# APC1.net
KiCad netlist of a schematic drawn in EAGLE
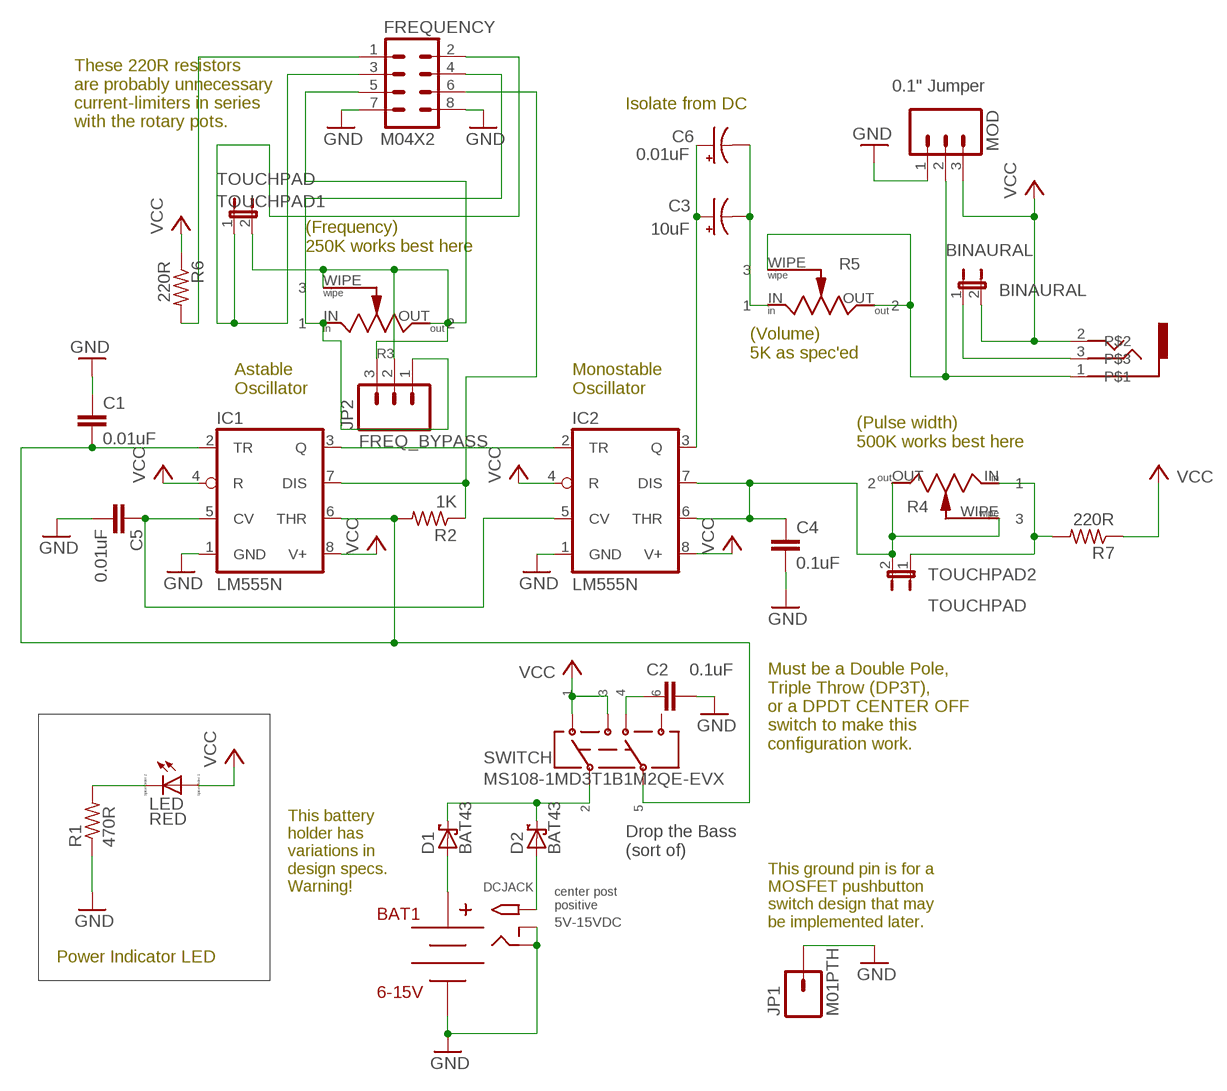
[diagram p0: schematic, sheet 1]

(export (version "E")
  (design (tool "Eeschema 10.0.6"))
  (components
    (comp (ref "BAT1")
      (value "6-15V")
      (footprint "eagle-import:BH9VPC")
      (libsource (lib "eagle-import") (part "BH-9VPC"))
    )
    (comp (ref "BINAURAL")
      (value "BINAURAL")
      (footprint "eagle-import:JP1")
      (libsource (lib "eagle-import") (part "JP1E"))
    )
    (comp (ref "C1")
      (value "0.01uF")
      (footprint "eagle-import:C050-024X044")
      (libsource (lib "eagle-import") (part "C-EU050-024X044"))
    )
    (comp (ref "C2")
      (value "0.1uF")
      (footprint "eagle-import:C050-024X044")
      (libsource (lib "eagle-import") (part "C-EU050-024X044"))
    )
    (comp (ref "C3")
      (value "10uF")
      (footprint "eagle-import:E2,5-7")
      (libsource (lib "eagle-import") (part "CPOL-USE2.5-7"))
    )
    (comp (ref "C4")
      (value "0.1uF")
      (footprint "eagle-import:C050-024X044")
      (libsource (lib "eagle-import") (part "C-EU050-024X044"))
    )
    (comp (ref "C5")
      (value "0.01uF")
      (footprint "eagle-import:C050-024X044")
      (libsource (lib "eagle-import") (part "C-EU050-024X044"))
    )
    (comp (ref "C6")
      (value "0.01uF")
      (footprint "eagle-import:E2,5-7")
      (libsource (lib "eagle-import") (part "CPOL-USE2.5-7"))
    )
    (comp (ref "D1")
      (value "BAT43")
      (footprint "eagle-import:DO35-7")
      (libsource (lib "eagle-import") (part "SCHOTTKY-DIODEDO35-7"))
    )
    (comp (ref "D2")
      (value "BAT43")
      (footprint "eagle-import:DO35-7")
      (libsource (lib "eagle-import") (part "SCHOTTKY-DIODEDO35-7"))
    )
    (comp (ref "DCJACK")
      (value "PJ102A")
      (footprint "eagle-import:PJ-102A")
      (libsource (lib "eagle-import") (part "PJ102A"))
    )
    (comp (ref "FREQUENCY")
      (value "M04X2")
      (footprint "eagle-import:2X4")
      (libsource (lib "eagle-import") (part "M04X2"))
    )
    (comp (ref "IC1")
      (value "LM555N")
      (footprint "eagle-import:DIL08")
      (libsource (lib "eagle-import") (part "555NLM"))
    )
    (comp (ref "IC2")
      (value "LM555N")
      (footprint "eagle-import:DIL08")
      (libsource (lib "eagle-import") (part "555NLM"))
    )
    (comp (ref "JP1")
      (value "M01PTH")
      (footprint "eagle-import:1X01")
      (libsource (lib "eagle-import") (part "M01PTH"))
    )
    (comp (ref "JP2")
      (value "FREQ_BYPASS")
      (footprint "eagle-import:1X03_SMD_RA_MALE")
      (libsource (lib "eagle-import") (part "M03SMD_RA_MALE"))
    )
    (comp (ref "LED")
      (value "RED")
      (footprint "eagle-import:LED_LD260")
      (libsource (lib "eagle-import") (part "LED_ELD260"))
    )
    (comp (ref "LINE")
      (value "SJ-3523-SMT")
      (footprint "eagle-import:SJ352_AUDIOJACK")
      (libsource (lib "eagle-import") (part "SJ-3523-SMT"))
    )
    (comp (ref "MOD")
      (value "0.1\" Jumper")
      (footprint "eagle-import:1X03_LOCK")
      (libsource (lib "eagle-import") (part "M03LOCK"))
    )
    (comp (ref "R1")
      (value "470R")
      (footprint "eagle-import:0207_7")
      (libsource (lib "eagle-import") (part "R-US_0207/7"))
    )
    (comp (ref "R2")
      (value "1K")
      (footprint "eagle-import:0207_7")
      (libsource (lib "eagle-import") (part "R-US_0207/7"))
    )
    (comp (ref "R3")
      (value "CTS_UM296RE_SERIES_POTENTIOMETERUM296RE")
      (footprint "eagle-import:UM296RE_POTENTIOMETER")
      (libsource (lib "eagle-import") (part "CTS_UM296RE_SERIES_POTENTIOMETERUM296RE"))
    )
    (comp (ref "R4")
      (value "CTS_UM296RE_SERIES_POTENTIOMETERUM296RE")
      (footprint "eagle-import:UM296RE_POTENTIOMETER")
      (libsource (lib "eagle-import") (part "CTS_UM296RE_SERIES_POTENTIOMETERUM296RE"))
    )
    (comp (ref "R5")
      (value "CTS_UM296RE_SERIES_POTENTIOMETERUM296RE")
      (footprint "eagle-import:UM296RE_POTENTIOMETER")
      (libsource (lib "eagle-import") (part "CTS_UM296RE_SERIES_POTENTIOMETERUM296RE"))
    )
    (comp (ref "R6")
      (value "220R")
      (footprint "eagle-import:0207_7")
      (libsource (lib "eagle-import") (part "R-US_0207/7"))
    )
    (comp (ref "R7")
      (value "220R")
      (footprint "eagle-import:0207_7")
      (libsource (lib "eagle-import") (part "R-US_0207/7"))
    )
    (comp (ref "SWITCH")
      (value "MS108-1MD3T1B1M2QE-EVX")
      (footprint "eagle-import:MS108-1MD3T1B1M2QE-EVX")
      (libsource (lib "eagle-import") (part "MS108-1MD3T1B1M2QE-EVX"))
    )
    (comp (ref "TOUCHPAD1")
      (value "TOUCHPAD")
      (footprint "eagle-import:JP1")
      (libsource (lib "eagle-import") (part "JP1E"))
    )
    (comp (ref "TOUCHPAD2")
      (value "TOUCHPAD")
      (footprint "eagle-import:JP1")
      (libsource (lib "eagle-import") (part "JP1E"))
    )
  )
  (nets
    (net (code "1") (name "GND") (class "Default")
      (node (ref "BAT1") (pin "P$1") (pinfunction "V-_P$1") (pintype "power_in"))
      (node (ref "C1") (pin "1") (pinfunction "1_1") (pintype "passive"))
      (node (ref "C2") (pin "2") (pinfunction "2_2") (pintype "passive"))
      (node (ref "C4") (pin "2") (pinfunction "2_2") (pintype "passive"))
      (node (ref "C5") (pin "2") (pinfunction "2_2") (pintype "passive"))
      (node (ref "DCJACK") (pin "P$2") (pinfunction "RING_P$2") (pintype "bidirectional"))
      (node (ref "DCJACK") (pin "P$3") (pinfunction "RING_SW_P$3") (pintype "bidirectional"))
      (node (ref "FREQUENCY") (pin "7") (pinfunction "7_7") (pintype "passive"))
      (node (ref "FREQUENCY") (pin "8") (pinfunction "8_8") (pintype "passive"))
      (node (ref "IC1") (pin "1") (pinfunction "GND_1") (pintype "power_in"))
      (node (ref "IC2") (pin "1") (pinfunction "GND_1") (pintype "power_in"))
      (node (ref "JP1") (pin "1") (pinfunction "1_1") (pintype "passive"))
      (node (ref "MOD") (pin "1") (pinfunction "1_1") (pintype "passive"))
      (node (ref "R1") (pin "1") (pinfunction "1_1") (pintype "passive"))
    )
    (net (code "2") (name "Net-(BAT1-V+)") (class "Default")
      (node (ref "BAT1") (pin "P$2") (pinfunction "V+_P$2") (pintype "power_in"))
      (node (ref "D1") (pin "A") (pinfunction "A_A") (pintype "passive"))
    )
    (net (code "3") (name "Net-(DCJACK-TIP)") (class "Default")
      (node (ref "D2") (pin "A") (pinfunction "A_A") (pintype "passive"))
      (node (ref "DCJACK") (pin "P$1") (pinfunction "TIP_P$1") (pintype "bidirectional"))
    )
    (net (code "4") (name "Net-(FREQUENCY-Pad1)") (class "Default")
      (node (ref "FREQUENCY") (pin "1") (pinfunction "1_1") (pintype "passive"))
      (node (ref "R6") (pin "2") (pinfunction "2_2") (pintype "passive"))
    )
    (net (code "5") (name "Net-(FREQUENCY-Pad2)") (class "Default")
      (node (ref "FREQUENCY") (pin "2") (pinfunction "2_2") (pintype "passive"))
      (node (ref "FREQUENCY") (pin "3") (pinfunction "3_3") (pintype "passive"))
      (node (ref "TOUCHPAD1") (pin "1") (pinfunction "1_1") (pintype "passive"))
    )
    (net (code "6") (name "Net-(IC1-CV)") (class "Default")
      (node (ref "C5") (pin "1") (pinfunction "1_1") (pintype "passive"))
      (node (ref "IC1") (pin "5") (pinfunction "CV_5") (pintype "input"))
      (node (ref "IC2") (pin "5") (pinfunction "CV_5") (pintype "input"))
    )
    (net (code "7") (name "Net-(IC1-DIS)") (class "Default")
      (node (ref "FREQUENCY") (pin "6") (pinfunction "6_6") (pintype "passive"))
      (node (ref "IC1") (pin "7") (pinfunction "DIS_7") (pintype "input"))
      (node (ref "R2") (pin "1") (pinfunction "1_1") (pintype "passive"))
    )
    (net (code "8") (name "Net-(IC1-Q)") (class "Default")
      (node (ref "IC1") (pin "3") (pinfunction "Q_3") (pintype "output"))
      (node (ref "IC2") (pin "2") (pinfunction "TR_2") (pintype "input"))
    )
    (net (code "9") (name "Net-(IC1-THR)") (class "Default")
      (node (ref "C1") (pin "2") (pinfunction "2_2") (pintype "passive"))
      (node (ref "IC1") (pin "2") (pinfunction "TR_2") (pintype "input"))
      (node (ref "IC1") (pin "6") (pinfunction "THR_6") (pintype "input"))
      (node (ref "R2") (pin "2") (pinfunction "2_2") (pintype "passive"))
      (node (ref "SWITCH") (pin "P$5") (pinfunction "5_P$5") (pintype "bidirectional"))
    )
    (net (code "10") (name "Net-(IC2-DIS)") (class "Default")
      (node (ref "C4") (pin "1") (pinfunction "1_1") (pintype "passive"))
      (node (ref "IC2") (pin "6") (pinfunction "THR_6") (pintype "input"))
      (node (ref "IC2") (pin "7") (pinfunction "DIS_7") (pintype "input"))
      (node (ref "R4") (pin "OUT") (pinfunction "2_OUT") (pintype "passive"))
      (node (ref "R4") (pin "WIPE") (pinfunction "3_WIPE") (pintype "passive"))
      (node (ref "TOUCHPAD2") (pin "2") (pinfunction "2_2") (pintype "passive"))
    )
    (net (code "11") (name "Net-(IC2-Q)") (class "Default")
      (node (ref "C3") (pin "+") (pinfunction "+_+") (pintype "passive"))
      (node (ref "C6") (pin "+") (pinfunction "+_+") (pintype "passive"))
      (node (ref "IC2") (pin "3") (pinfunction "Q_3") (pintype "output"))
    )
    (net (code "12") (name "Net-(LED-C)") (class "Default")
      (node (ref "LED") (pin "K") (pinfunction "C_K") (pintype "passive"))
      (node (ref "R1") (pin "2") (pinfunction "2_2") (pintype "passive"))
    )
    (net (code "13") (name "Net-(LINE-P$1)") (class "Default")
      (node (ref "LINE") (pin "1") (pinfunction "P$1_1") (pintype "bidirectional"))
      (node (ref "MOD") (pin "2") (pinfunction "2_2") (pintype "passive"))
      (node (ref "R5") (pin "OUT") (pinfunction "2_OUT") (pintype "passive"))
      (node (ref "R5") (pin "WIPE") (pinfunction "3_WIPE") (pintype "passive"))
    )
    (net (code "14") (name "Net-(LINE-P$3)") (class "Default")
      (node (ref "BINAURAL") (pin "1") (pinfunction "1_1") (pintype "passive"))
      (node (ref "LINE") (pin "3") (pinfunction "P$3_3") (pintype "bidirectional"))
    )
    (net (code "15") (name "Net-(R3-1)") (class "Default")
      (node (ref "FREQUENCY") (pin "4") (pinfunction "4_4") (pintype "passive"))
      (node (ref "JP2") (pin "1") (pinfunction "1_1") (pintype "passive"))
      (node (ref "R3") (pin "IN") (pinfunction "1_IN") (pintype "passive"))
    )
    (net (code "16") (name "Net-(R3-2)") (class "Default")
      (node (ref "FREQUENCY") (pin "5") (pinfunction "5_5") (pintype "passive"))
      (node (ref "JP2") (pin "2") (pinfunction "2_2") (pintype "passive"))
      (node (ref "JP2") (pin "3") (pinfunction "3_3") (pintype "passive"))
      (node (ref "R3") (pin "OUT") (pinfunction "2_OUT") (pintype "passive"))
      (node (ref "R3") (pin "WIPE") (pinfunction "3_WIPE") (pintype "passive"))
      (node (ref "TOUCHPAD1") (pin "2") (pinfunction "2_2") (pintype "passive"))
    )
    (net (code "17") (name "Net-(R4-1)") (class "Default")
      (node (ref "R4") (pin "IN") (pinfunction "1_IN") (pintype "passive"))
      (node (ref "R7") (pin "2") (pinfunction "2_2") (pintype "passive"))
      (node (ref "TOUCHPAD2") (pin "1") (pinfunction "1_1") (pintype "passive"))
    )
    (net (code "18") (name "Net-(R5-1)") (class "Default")
      (node (ref "C3") (pin "-") (pinfunction "-_-") (pintype "passive"))
      (node (ref "C6") (pin "-") (pinfunction "-_-") (pintype "passive"))
      (node (ref "R5") (pin "IN") (pinfunction "1_IN") (pintype "passive"))
    )
    (net (code "19") (name "Net-(SWITCH-2)") (class "Default")
      (node (ref "D1") (pin "C") (pinfunction "C_C") (pintype "passive"))
      (node (ref "D2") (pin "C") (pinfunction "C_C") (pintype "passive"))
      (node (ref "SWITCH") (pin "P$2") (pinfunction "2_P$2") (pintype "bidirectional"))
    )
    (net (code "20") (name "Net-(SWITCH-4)") (class "Default")
      (node (ref "C2") (pin "1") (pinfunction "1_1") (pintype "passive"))
      (node (ref "SWITCH") (pin "P$4") (pinfunction "4_P$4") (pintype "bidirectional"))
    )
    (net (code "21") (name "VCC") (class "Default")
      (node (ref "BINAURAL") (pin "2") (pinfunction "2_2") (pintype "passive"))
      (node (ref "IC1") (pin "4") (pinfunction "R_4") (pintype "input"))
      (node (ref "IC1") (pin "8") (pinfunction "V+_8") (pintype "power_in"))
      (node (ref "IC2") (pin "4") (pinfunction "R_4") (pintype "input"))
      (node (ref "IC2") (pin "8") (pinfunction "V+_8") (pintype "power_in"))
      (node (ref "LED") (pin "A") (pinfunction "A_A") (pintype "passive"))
      (node (ref "LINE") (pin "2") (pinfunction "P$2_2") (pintype "bidirectional"))
      (node (ref "MOD") (pin "3") (pinfunction "3_3") (pintype "passive"))
      (node (ref "R6") (pin "1") (pinfunction "1_1") (pintype "passive"))
      (node (ref "R7") (pin "1") (pinfunction "1_1") (pintype "passive"))
      (node (ref "SWITCH") (pin "P$1") (pinfunction "1_P$1") (pintype "bidirectional"))
      (node (ref "SWITCH") (pin "P$3") (pinfunction "3_P$3") (pintype "bidirectional"))
    )
    (net (code "22") (name "unconnected-(SWITCH-6-PadP$6)") (class "Default")
      (node (ref "SWITCH") (pin "P$6") (pinfunction "6_P$6") (pintype "bidirectional"))
    )
  )
)
